# servodengen.net
KiCad netlist of a schematic drawn in EAGLE
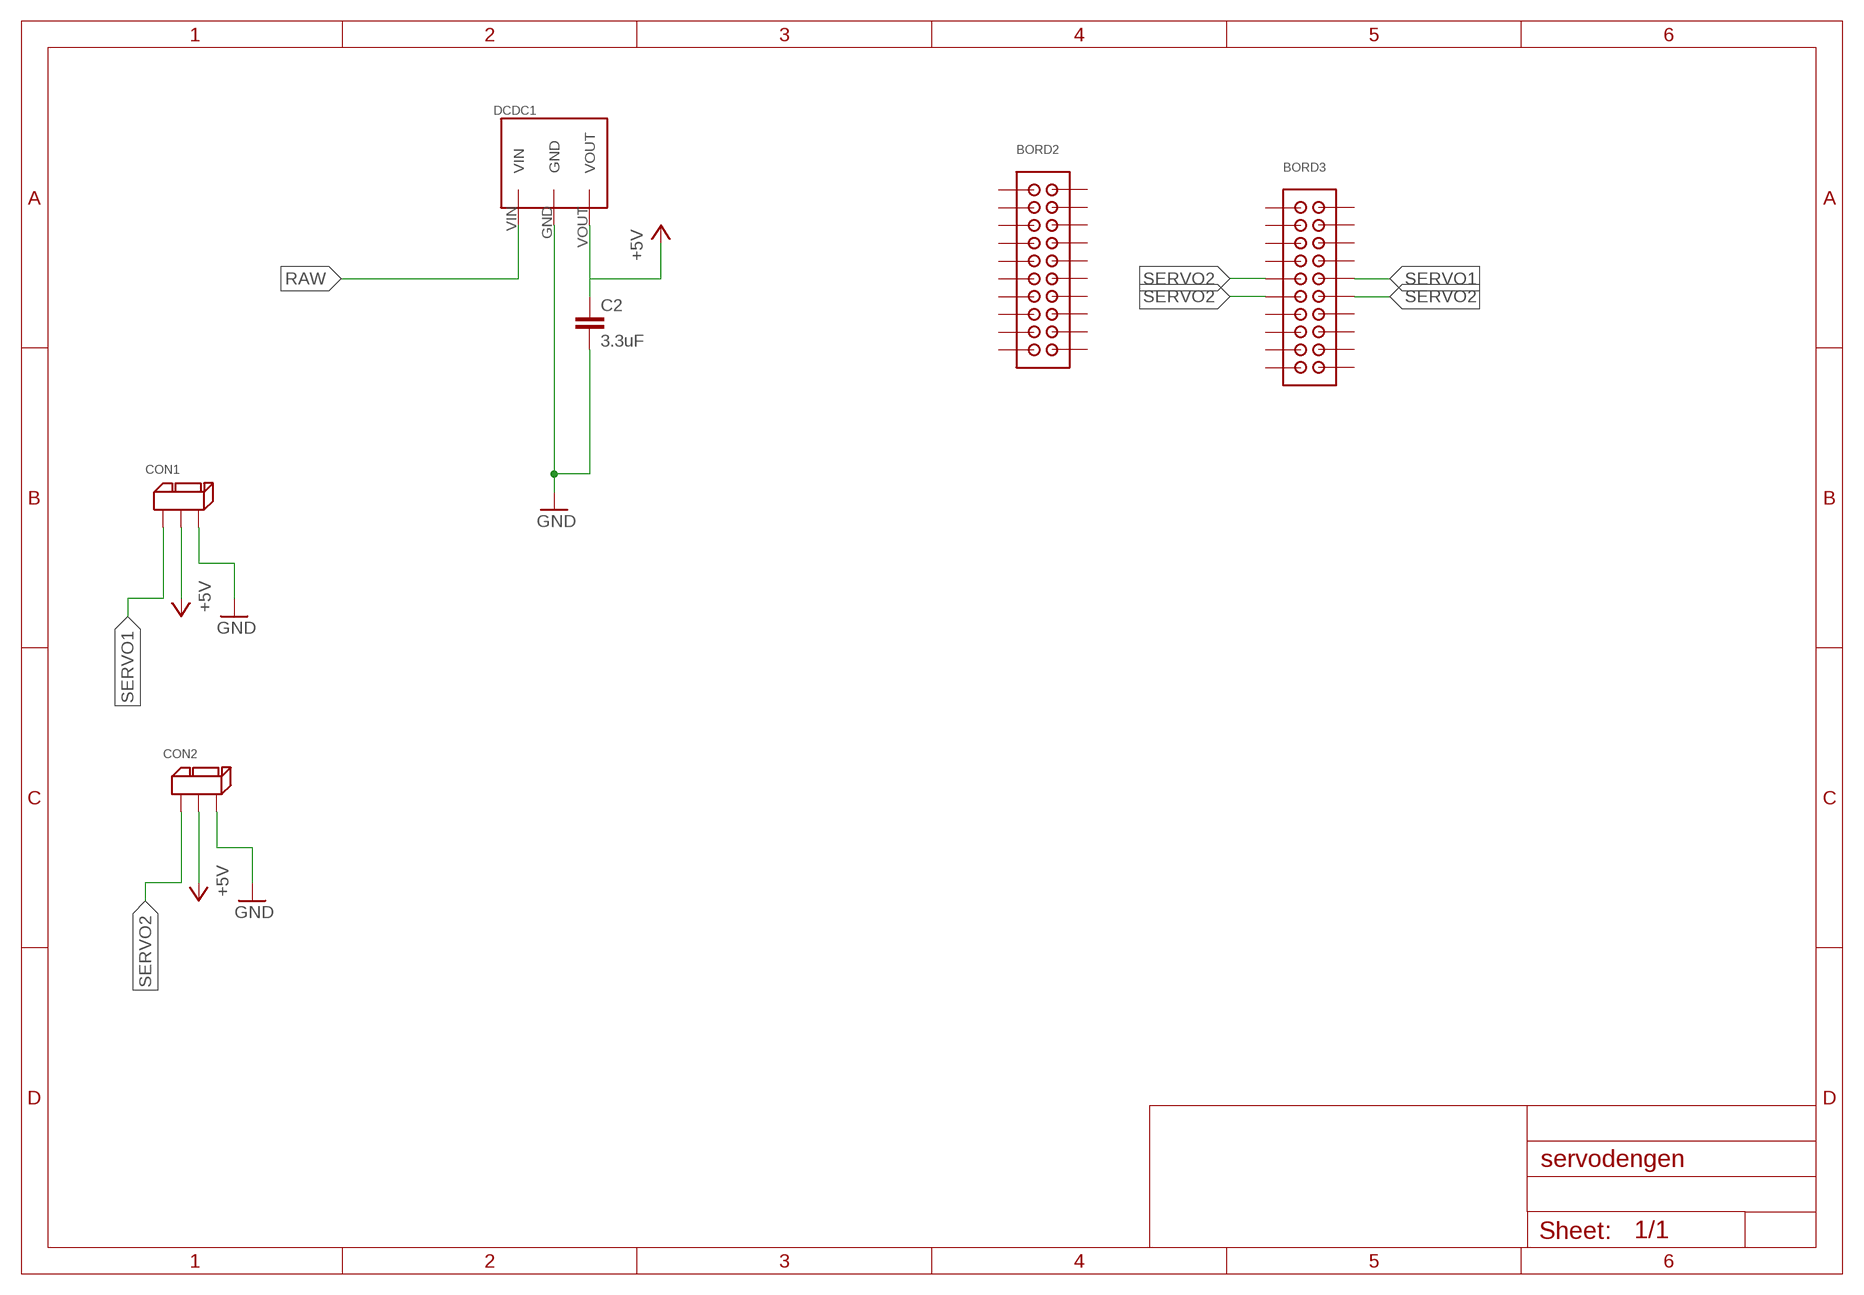
[diagram p0: schematic, sheet 1]

(export (version "E")
  (design (tool "Eeschema 10.0.6"))
  (components
    (comp (ref "BORD2")
      (value "2X10")
      (footprint "eagle-import:2X10")
      (libsource (lib "eagle-import") (part "2X10"))
    )
    (comp (ref "BORD3")
      (value "2X10")
      (footprint "eagle-import:2X10")
      (libsource (lib "eagle-import") (part "2X10"))
    )
    (comp (ref "C2")
      (value "3.3uF")
      (footprint "eagle-import:C025-024X044")
      (libsource (lib "eagle-import") (part "C-EU025-024X044"))
    )
    (comp (ref "CON1")
      (value "3PIN")
      (footprint "eagle-import:3PIN")
      (libsource (lib "eagle-import") (part "3PIN"))
    )
    (comp (ref "CON2")
      (value "3PIN")
      (footprint "eagle-import:3PIN")
      (libsource (lib "eagle-import") (part "3PIN"))
    )
    (comp (ref "DCDC1")
      (value "5V1A_M78AR05-1")
      (footprint "eagle-import:5V1A_M78AR05-1")
      (libsource (lib "eagle-import") (part "5V1A_M78AR05-1"))
    )
  )
  (nets
    (net (code "1") (name "+5V") (class "Default")
      (node (ref "C2") (pin "1") (pinfunction "1_1") (pintype "passive"))
      (node (ref "CON1") (pin "P$2") (pinfunction "P$2_P$2") (pintype "bidirectional"))
      (node (ref "CON2") (pin "P$2") (pinfunction "P$2_P$2") (pintype "bidirectional"))
      (node (ref "DCDC1") (pin "VOUT") (pinfunction "VOUT_VOUT") (pintype "bidirectional"))
    )
    (net (code "2") (name "GND") (class "Default")
      (node (ref "C2") (pin "2") (pinfunction "2_2") (pintype "passive"))
      (node (ref "CON1") (pin "P$3") (pinfunction "P$3_P$3") (pintype "bidirectional"))
      (node (ref "CON2") (pin "P$3") (pinfunction "P$3_P$3") (pintype "bidirectional"))
      (node (ref "DCDC1") (pin "GND") (pinfunction "GND_GND") (pintype "bidirectional"))
    )
    (net (code "3") (name "RAW") (class "Default")
      (node (ref "DCDC1") (pin "VIN") (pinfunction "VIN_VIN") (pintype "bidirectional"))
    )
    (net (code "4") (name "SERVO1") (class "Default")
      (node (ref "BORD3") (pin "P$10") (pinfunction "P$10_P$10") (pintype "bidirectional"))
      (node (ref "CON1") (pin "P$1") (pinfunction "P$1_P$1") (pintype "bidirectional"))
    )
    (net (code "5") (name "SERVO2") (class "Default")
      (node (ref "BORD3") (pin "P$11") (pinfunction "P$11_P$11") (pintype "bidirectional"))
      (node (ref "BORD3") (pin "P$12") (pinfunction "P$12_P$12") (pintype "bidirectional"))
      (node (ref "BORD3") (pin "P$9") (pinfunction "P$9_P$9") (pintype "bidirectional"))
      (node (ref "CON2") (pin "P$1") (pinfunction "P$1_P$1") (pintype "bidirectional"))
    )
    (net (code "6") (name "unconnected-(BORD2-PadP$1)") (class "Default")
      (node (ref "BORD2") (pin "P$1") (pinfunction "P$1_P$1") (pintype "bidirectional"))
    )
    (net (code "7") (name "unconnected-(BORD2-PadP$2)") (class "Default")
      (node (ref "BORD2") (pin "P$2") (pinfunction "P$2_P$2") (pintype "bidirectional"))
    )
    (net (code "8") (name "unconnected-(BORD2-PadP$3)") (class "Default")
      (node (ref "BORD2") (pin "P$3") (pinfunction "P$3_P$3") (pintype "bidirectional"))
    )
    (net (code "9") (name "unconnected-(BORD2-PadP$4)") (class "Default")
      (node (ref "BORD2") (pin "P$4") (pinfunction "P$4_P$4") (pintype "bidirectional"))
    )
    (net (code "10") (name "unconnected-(BORD2-PadP$5)") (class "Default")
      (node (ref "BORD2") (pin "P$5") (pinfunction "P$5_P$5") (pintype "bidirectional"))
    )
    (net (code "11") (name "unconnected-(BORD2-PadP$6)") (class "Default")
      (node (ref "BORD2") (pin "P$6") (pinfunction "P$6_P$6") (pintype "bidirectional"))
    )
    (net (code "12") (name "unconnected-(BORD2-PadP$7)") (class "Default")
      (node (ref "BORD2") (pin "P$7") (pinfunction "P$7_P$7") (pintype "bidirectional"))
    )
    (net (code "13") (name "unconnected-(BORD2-PadP$8)") (class "Default")
      (node (ref "BORD2") (pin "P$8") (pinfunction "P$8_P$8") (pintype "bidirectional"))
    )
    (net (code "14") (name "unconnected-(BORD2-PadP$9)") (class "Default")
      (node (ref "BORD2") (pin "P$9") (pinfunction "P$9_P$9") (pintype "bidirectional"))
    )
    (net (code "15") (name "unconnected-(BORD2-PadP$10)") (class "Default")
      (node (ref "BORD2") (pin "P$10") (pinfunction "P$10_P$10") (pintype "bidirectional"))
    )
    (net (code "16") (name "unconnected-(BORD2-PadP$11)") (class "Default")
      (node (ref "BORD2") (pin "P$11") (pinfunction "P$11_P$11") (pintype "bidirectional"))
    )
    (net (code "17") (name "unconnected-(BORD2-PadP$12)") (class "Default")
      (node (ref "BORD2") (pin "P$12") (pinfunction "P$12_P$12") (pintype "bidirectional"))
    )
    (net (code "18") (name "unconnected-(BORD2-PadP$13)") (class "Default")
      (node (ref "BORD2") (pin "P$13") (pinfunction "P$13_P$13") (pintype "bidirectional"))
    )
    (net (code "19") (name "unconnected-(BORD2-PadP$14)") (class "Default")
      (node (ref "BORD2") (pin "P$14") (pinfunction "P$14_P$14") (pintype "bidirectional"))
    )
    (net (code "20") (name "unconnected-(BORD2-PadP$15)") (class "Default")
      (node (ref "BORD2") (pin "P$15") (pinfunction "P$15_P$15") (pintype "bidirectional"))
    )
    (net (code "21") (name "unconnected-(BORD2-PadP$16)") (class "Default")
      (node (ref "BORD2") (pin "P$16") (pinfunction "P$16_P$16") (pintype "bidirectional"))
    )
    (net (code "22") (name "unconnected-(BORD2-PadP$17)") (class "Default")
      (node (ref "BORD2") (pin "P$17") (pinfunction "P$17_P$17") (pintype "bidirectional"))
    )
    (net (code "23") (name "unconnected-(BORD2-PadP$18)") (class "Default")
      (node (ref "BORD2") (pin "P$18") (pinfunction "P$18_P$18") (pintype "bidirectional"))
    )
    (net (code "24") (name "unconnected-(BORD2-PadP$19)") (class "Default")
      (node (ref "BORD2") (pin "P$19") (pinfunction "P$19_P$19") (pintype "bidirectional"))
    )
    (net (code "25") (name "unconnected-(BORD2-PadP$20)") (class "Default")
      (node (ref "BORD2") (pin "P$20") (pinfunction "P$20_P$20") (pintype "bidirectional"))
    )
    (net (code "26") (name "unconnected-(BORD3-PadP$1)") (class "Default")
      (node (ref "BORD3") (pin "P$1") (pinfunction "P$1_P$1") (pintype "bidirectional"))
    )
    (net (code "27") (name "unconnected-(BORD3-PadP$2)") (class "Default")
      (node (ref "BORD3") (pin "P$2") (pinfunction "P$2_P$2") (pintype "bidirectional"))
    )
    (net (code "28") (name "unconnected-(BORD3-PadP$3)") (class "Default")
      (node (ref "BORD3") (pin "P$3") (pinfunction "P$3_P$3") (pintype "bidirectional"))
    )
    (net (code "29") (name "unconnected-(BORD3-PadP$4)") (class "Default")
      (node (ref "BORD3") (pin "P$4") (pinfunction "P$4_P$4") (pintype "bidirectional"))
    )
    (net (code "30") (name "unconnected-(BORD3-PadP$5)") (class "Default")
      (node (ref "BORD3") (pin "P$5") (pinfunction "P$5_P$5") (pintype "bidirectional"))
    )
    (net (code "31") (name "unconnected-(BORD3-PadP$6)") (class "Default")
      (node (ref "BORD3") (pin "P$6") (pinfunction "P$6_P$6") (pintype "bidirectional"))
    )
    (net (code "32") (name "unconnected-(BORD3-PadP$7)") (class "Default")
      (node (ref "BORD3") (pin "P$7") (pinfunction "P$7_P$7") (pintype "bidirectional"))
    )
    (net (code "33") (name "unconnected-(BORD3-PadP$8)") (class "Default")
      (node (ref "BORD3") (pin "P$8") (pinfunction "P$8_P$8") (pintype "bidirectional"))
    )
    (net (code "34") (name "unconnected-(BORD3-PadP$13)") (class "Default")
      (node (ref "BORD3") (pin "P$13") (pinfunction "P$13_P$13") (pintype "bidirectional"))
    )
    (net (code "35") (name "unconnected-(BORD3-PadP$14)") (class "Default")
      (node (ref "BORD3") (pin "P$14") (pinfunction "P$14_P$14") (pintype "bidirectional"))
    )
    (net (code "36") (name "unconnected-(BORD3-PadP$15)") (class "Default")
      (node (ref "BORD3") (pin "P$15") (pinfunction "P$15_P$15") (pintype "bidirectional"))
    )
    (net (code "37") (name "unconnected-(BORD3-PadP$16)") (class "Default")
      (node (ref "BORD3") (pin "P$16") (pinfunction "P$16_P$16") (pintype "bidirectional"))
    )
    (net (code "38") (name "unconnected-(BORD3-PadP$17)") (class "Default")
      (node (ref "BORD3") (pin "P$17") (pinfunction "P$17_P$17") (pintype "bidirectional"))
    )
    (net (code "39") (name "unconnected-(BORD3-PadP$18)") (class "Default")
      (node (ref "BORD3") (pin "P$18") (pinfunction "P$18_P$18") (pintype "bidirectional"))
    )
    (net (code "40") (name "unconnected-(BORD3-PadP$19)") (class "Default")
      (node (ref "BORD3") (pin "P$19") (pinfunction "P$19_P$19") (pintype "bidirectional"))
    )
    (net (code "41") (name "unconnected-(BORD3-PadP$20)") (class "Default")
      (node (ref "BORD3") (pin "P$20") (pinfunction "P$20_P$20") (pintype "bidirectional"))
    )
  )
)
